# HighSideDriver.net
KiCad netlist of a schematic drawn in Altium Designer
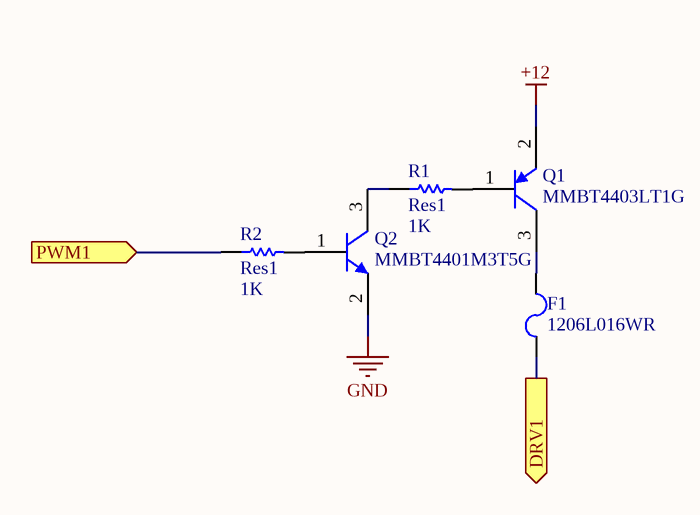
[diagram p0: HighSideDriver.SchDoc]

(export (version "E")
  (design (tool "Eeschema 10.0.6"))
  (components
    (comp (ref "F1")
      (value "1206L016WR")
      (footprint "LFUS-1206L016WR_V")
      (description "Resettable Fuse, 30 V, 100 A, 4.5 Ohm, -40 to 85 degC, 1206 (3216 Metric), RoHS, Tape and Reel")
      (fields (field (name "MANUFACTURER") "Littelfuse"))
      (libsource (lib "Altium Content Vault") (part "FUSE-2"))
    )
    (comp (ref "Q1")
      (value "MMBT4403LT1G")
      (footprint "ONSC-SOT-23-3-318-08_V")
      (description "Switching Transistor, PNP Silicon, 3-Pin SOT-23, Pb-Free, Tape and Reel")
      (fields (field (name "MANUFACTURER") "On Semiconductor"))
      (libsource (lib "Altium Content Vault") (part "CMP-1048-00539-1"))
    )
    (comp (ref "Q2")
      (value "MMBT4401M3T5G")
      (footprint "ONSC-SOT-23-3-318-08_V")
      (description "Switching Transistor, NPN Silicon, 3-Pin SOT-23, Pb-Free, Tape and Reel")
      (fields (field (name "MANUFACTURER") "On Semiconductor") (field (name "PARTNUMBER") "MMBT4401LT3G"))
      (libsource (lib "Altium Content Vault") (part "CMP-1048-00548-1"))
    )
    (comp (ref "R1")
      (value "Res1")
      (footprint "J1-0603")
      (description "Resistor")
      (fields (field (name "ALTIUM_VALUE") "1K") (field (name "PUBLISHER") "Altium Limited"))
      (libsource (lib "Miscellaneous Devices") (part "Res1"))
    )
    (comp (ref "R2")
      (value "Res1")
      (footprint "J1-0603")
      (description "Resistor")
      (fields (field (name "ALTIUM_VALUE") "1K") (field (name "PUBLISHER") "Altium Limited"))
      (libsource (lib "Miscellaneous Devices") (part "Res1"))
    )
  )
  (nets
    (net (code "1") (name "+12") (class "Default")
      (node (ref "Q1") (pin "2") (pinfunction "E_2") (pintype "passive"))
    )
    (net (code "2") (name "/DRV1") (class "Default")
      (node (ref "F1") (pin "1") (pinfunction "1_1") (pintype "passive"))
    )
    (net (code "3") (name "/PWM1") (class "Default")
      (node (ref "R2") (pin "1") (pinfunction "1_1") (pintype "passive"))
    )
    (net (code "4") (name "GND") (class "Default")
      (node (ref "Q2") (pin "2") (pinfunction "E_2") (pintype "passive"))
    )
    (net (code "5") (name "Net-(Q1-B)") (class "Default")
      (node (ref "Q1") (pin "1") (pinfunction "B_1") (pintype "passive"))
      (node (ref "R1") (pin "2") (pinfunction "2_2") (pintype "passive"))
    )
    (net (code "6") (name "Net-(Q1-C)") (class "Default")
      (node (ref "F1") (pin "2") (pinfunction "2_2") (pintype "passive"))
      (node (ref "Q1") (pin "3") (pinfunction "C_3") (pintype "passive"))
    )
    (net (code "7") (name "Net-(Q2-B)") (class "Default")
      (node (ref "Q2") (pin "1") (pinfunction "B_1") (pintype "passive"))
      (node (ref "R2") (pin "2") (pinfunction "2_2") (pintype "passive"))
    )
    (net (code "8") (name "Net-(Q2-C)") (class "Default")
      (node (ref "Q2") (pin "3") (pinfunction "C_3") (pintype "passive"))
      (node (ref "R1") (pin "1") (pinfunction "1_1") (pintype "passive"))
    )
  )
)
